# fujiBLEboard.net
KiCad netlist of a schematic drawn in EAGLE
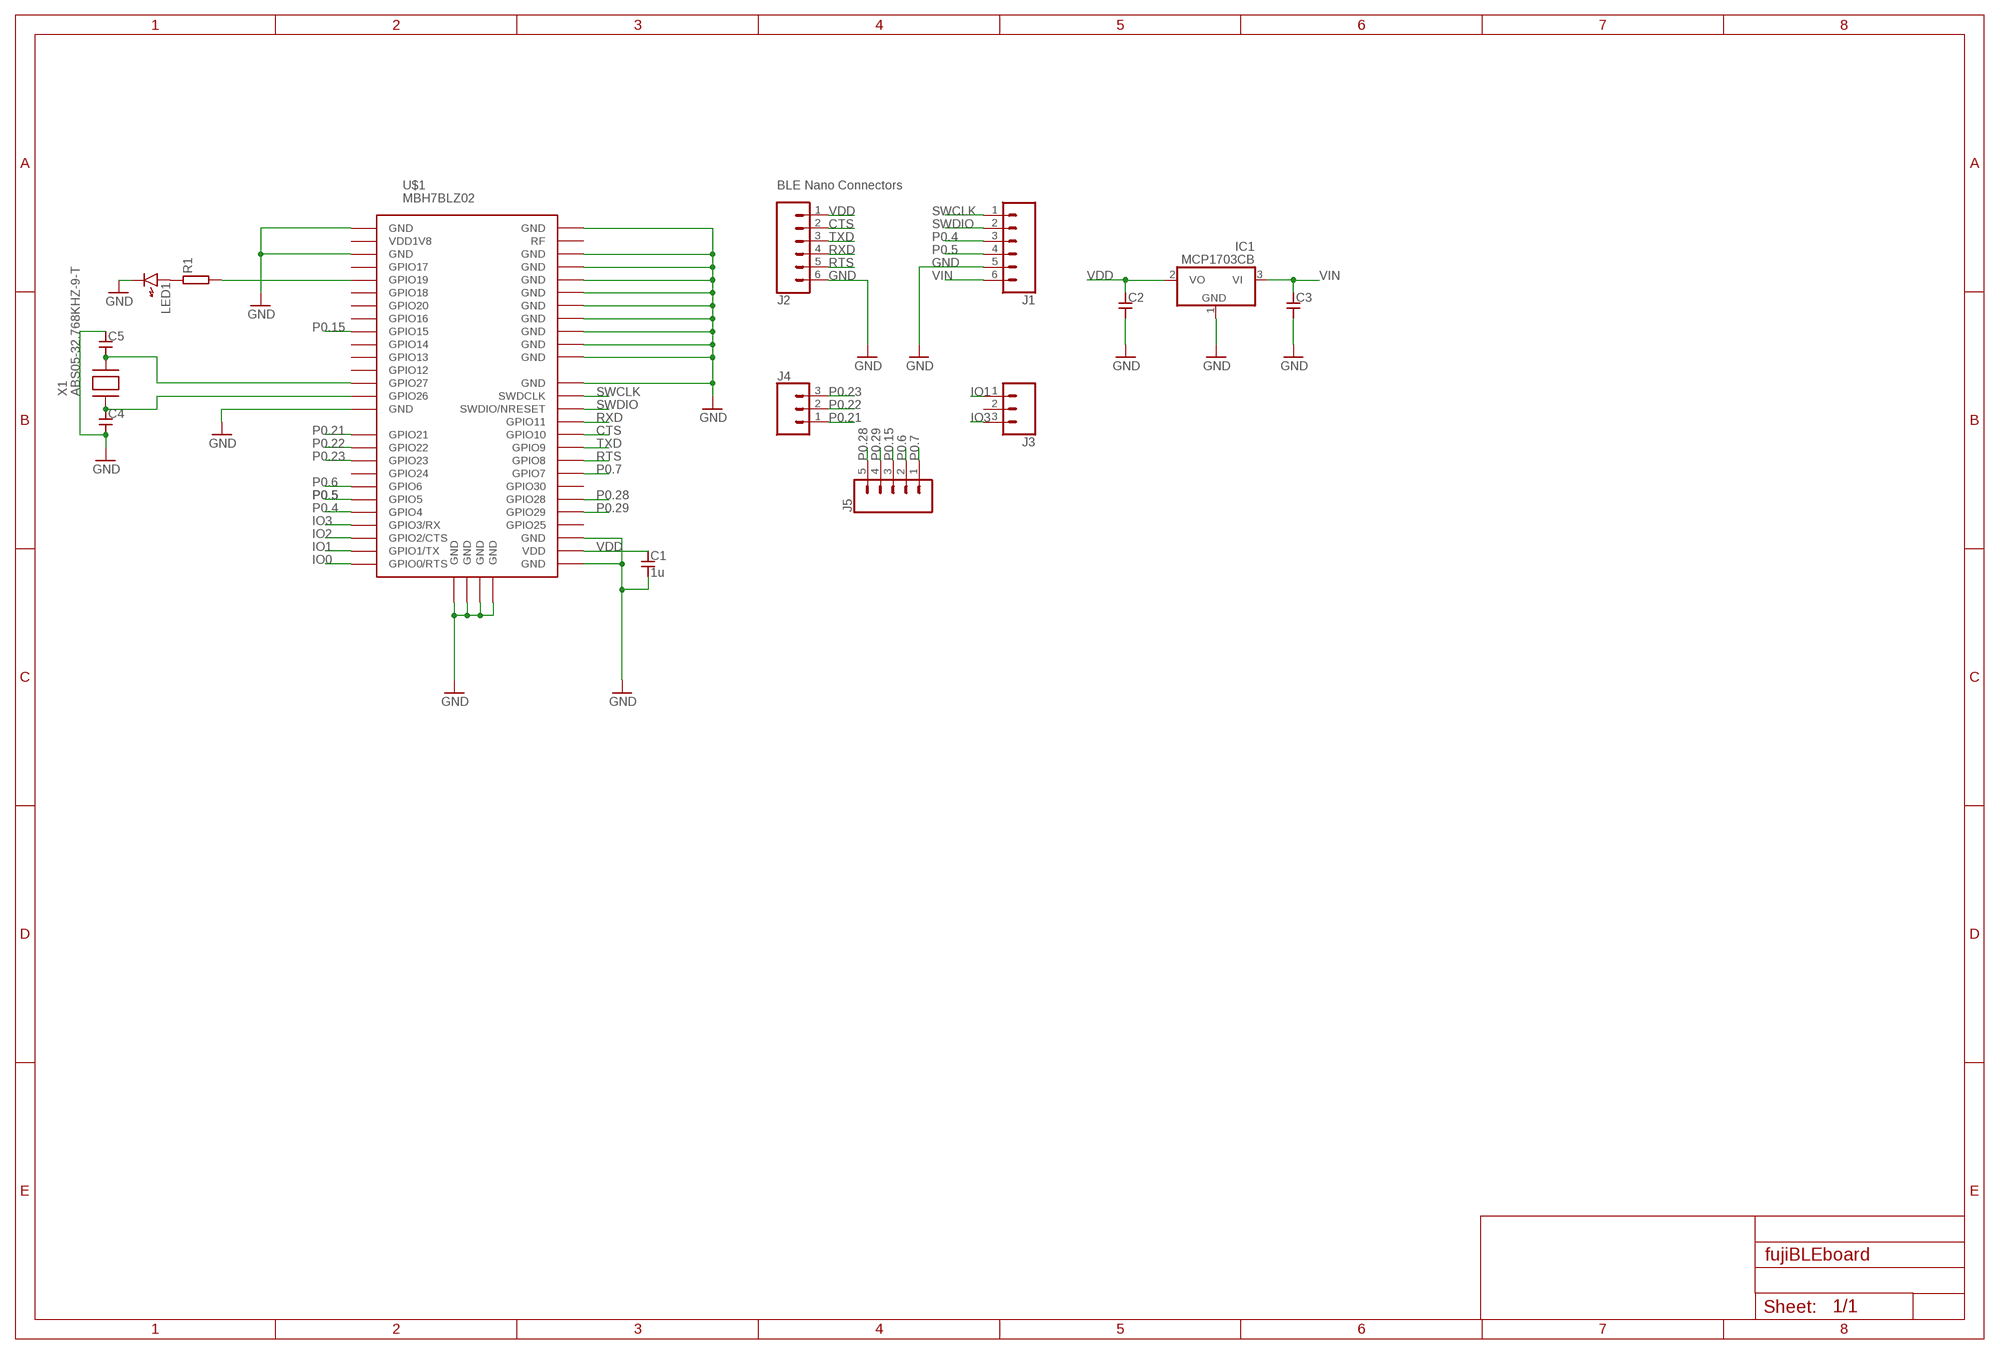
[diagram p0: schematic, sheet 1]

(export (version "E")
  (design (tool "Eeschema 10.0.6"))
  (components
    (comp (ref "C1")
      (value "1u")
      (footprint "eagle-import:SMD1608_REDUCED")
      (libsource (lib "eagle-import") (part "CAPACITOR1608_REDUCED"))
    )
    (comp (ref "C2")
      (value "CAPACITOR1608_REDUCED")
      (footprint "eagle-import:SMD1608_REDUCED")
      (libsource (lib "eagle-import") (part "CAPACITOR1608_REDUCED"))
    )
    (comp (ref "C3")
      (value "CAPACITOR1608_REDUCED")
      (footprint "eagle-import:SMD1608_REDUCED")
      (libsource (lib "eagle-import") (part "CAPACITOR1608_REDUCED"))
    )
    (comp (ref "C4")
      (value "CAPACITOR1005")
      (footprint "eagle-import:SMD1005")
      (libsource (lib "eagle-import") (part "CAPACITOR1005"))
    )
    (comp (ref "C5")
      (value "CAPACITOR1005")
      (footprint "eagle-import:SMD1005")
      (libsource (lib "eagle-import") (part "CAPACITOR1005"))
    )
    (comp (ref "IC1")
      (value "MCP1703CB")
      (footprint "eagle-import:SOT23")
      (libsource (lib "eagle-import") (part "MCP1703CB"))
    )
    (comp (ref "J1")
      (value "CONN_06NO_SILK_FEMALE_PTH")
      (footprint "eagle-import:1X06_NO_SILK")
      (libsource (lib "eagle-import") (part "CONN_06NO_SILK_FEMALE_PTH"))
    )
    (comp (ref "J2")
      (value "CONN_06NO_SILK_FEMALE_PTH")
      (footprint "eagle-import:1X06_NO_SILK")
      (libsource (lib "eagle-import") (part "CONN_06NO_SILK_FEMALE_PTH"))
    )
    (comp (ref "J3")
      (value "CONN_031X03_NO_SILK")
      (footprint "eagle-import:1X03_NO_SILK")
      (libsource (lib "eagle-import") (part "CONN_031X03_NO_SILK"))
    )
    (comp (ref "J4")
      (value "CONN_031X03_NO_SILK")
      (footprint "eagle-import:1X03_NO_SILK")
      (libsource (lib "eagle-import") (part "CONN_031X03_NO_SILK"))
    )
    (comp (ref "J5")
      (value "CONN_05NO_SILK")
      (footprint "eagle-import:1X05_NO_SILK")
      (libsource (lib "eagle-import") (part "CONN_05NO_SILK"))
    )
    (comp (ref "LED1")
      (value "LED1608_REDUCED")
      (footprint "eagle-import:LED1608_REDUCED")
      (libsource (lib "eagle-import") (part "LED1608_REDUCED"))
    )
    (comp (ref "R1")
      (value "RESISTOR1005")
      (footprint "eagle-import:SMD1005")
      (libsource (lib "eagle-import") (part "RESISTOR1005"))
    )
    (comp (ref "U$1")
      (value "MBH7BLZ02")
      (footprint "eagle-import:MBH7BLZ02")
      (libsource (lib "eagle-import") (part "MBH7BLZ02"))
    )
    (comp (ref "X1")
      (value "ABS05-32.768KHZ-9-T")
      (footprint "eagle-import:SMD1610")
      (libsource (lib "eagle-import") (part "ABS05-32.768KHZ-9-T"))
    )
  )
  (nets
    (net (code "1") (name "/CTS") (class "Default")
      (node (ref "J2") (pin "2") (pinfunction "2_2") (pintype "passive"))
      (node (ref "U$1") (pin "P$37") (pinfunction "GPIO10_P$37") (pintype "bidirectional"))
    )
    (net (code "2") (name "/IO0") (class "Default")
      (node (ref "U$1") (pin "P$26") (pinfunction "GPIO0/RTS_P$26") (pintype "bidirectional"))
    )
    (net (code "3") (name "/IO1") (class "Default")
      (node (ref "J3") (pin "1") (pinfunction "1_1") (pintype "passive"))
      (node (ref "U$1") (pin "P$25") (pinfunction "GPIO1/TX_P$25") (pintype "bidirectional"))
    )
    (net (code "4") (name "/IO2") (class "Default")
      (node (ref "U$1") (pin "P$24") (pinfunction "GPIO2/CTS_P$24") (pintype "bidirectional"))
    )
    (net (code "5") (name "/IO3") (class "Default")
      (node (ref "J3") (pin "3") (pinfunction "3_3") (pintype "passive"))
      (node (ref "U$1") (pin "P$23") (pinfunction "GPIO3/RX_P$23") (pintype "bidirectional"))
    )
    (net (code "6") (name "/P0.4") (class "Default")
      (node (ref "J1") (pin "3") (pinfunction "3_3") (pintype "passive"))
      (node (ref "U$1") (pin "P$22") (pinfunction "GPIO4_P$22") (pintype "bidirectional"))
    )
    (net (code "7") (name "/P0.5") (class "Default")
      (node (ref "J1") (pin "4") (pinfunction "4_4") (pintype "passive"))
      (node (ref "U$1") (pin "P$21") (pinfunction "GPIO5_P$21") (pintype "bidirectional"))
    )
    (net (code "8") (name "/P0.6") (class "Default")
      (node (ref "J5") (pin "2") (pinfunction "2_2") (pintype "passive"))
      (node (ref "U$1") (pin "P$20") (pinfunction "GPIO6_P$20") (pintype "bidirectional"))
    )
    (net (code "9") (name "/P0.7") (class "Default")
      (node (ref "J5") (pin "1") (pinfunction "1_1") (pintype "passive"))
      (node (ref "U$1") (pin "P$34") (pinfunction "GPIO7_P$34") (pintype "bidirectional"))
    )
    (net (code "10") (name "/P0.15") (class "Default")
      (node (ref "J5") (pin "3") (pinfunction "3_3") (pintype "passive"))
      (node (ref "U$1") (pin "P$9") (pinfunction "GPIO15_P$9") (pintype "bidirectional"))
    )
    (net (code "11") (name "/P0.21") (class "Default")
      (node (ref "J4") (pin "1") (pinfunction "1_1") (pintype "passive"))
      (node (ref "U$1") (pin "P$16") (pinfunction "GPIO21_P$16") (pintype "bidirectional"))
    )
    (net (code "12") (name "/P0.22") (class "Default")
      (node (ref "J4") (pin "2") (pinfunction "2_2") (pintype "passive"))
      (node (ref "U$1") (pin "P$17") (pinfunction "GPIO22_P$17") (pintype "bidirectional"))
    )
    (net (code "13") (name "/P0.23") (class "Default")
      (node (ref "J4") (pin "3") (pinfunction "3_3") (pintype "passive"))
      (node (ref "U$1") (pin "P$18") (pinfunction "GPIO23_P$18") (pintype "bidirectional"))
    )
    (net (code "14") (name "/P0.28") (class "Default")
      (node (ref "J5") (pin "5") (pinfunction "5_5") (pintype "passive"))
      (node (ref "U$1") (pin "P$32") (pinfunction "GPIO28_P$32") (pintype "bidirectional"))
    )
    (net (code "15") (name "/P0.29") (class "Default")
      (node (ref "J5") (pin "4") (pinfunction "4_4") (pintype "passive"))
      (node (ref "U$1") (pin "P$31") (pinfunction "GPIO29_P$31") (pintype "bidirectional"))
    )
    (net (code "16") (name "/RTS") (class "Default")
      (node (ref "J2") (pin "5") (pinfunction "5_5") (pintype "passive"))
      (node (ref "U$1") (pin "P$35") (pinfunction "GPIO8_P$35") (pintype "bidirectional"))
    )
    (net (code "17") (name "/RXD") (class "Default")
      (node (ref "J2") (pin "4") (pinfunction "4_4") (pintype "passive"))
      (node (ref "U$1") (pin "P$38") (pinfunction "GPIO11_P$38") (pintype "bidirectional"))
    )
    (net (code "18") (name "/SWCLK") (class "Default")
      (node (ref "J1") (pin "1") (pinfunction "1_1") (pintype "passive"))
      (node (ref "U$1") (pin "P$40") (pinfunction "SWDCLK_P$40") (pintype "bidirectional"))
    )
    (net (code "19") (name "/SWDIO") (class "Default")
      (node (ref "J1") (pin "2") (pinfunction "2_2") (pintype "passive"))
      (node (ref "U$1") (pin "P$39") (pinfunction "SWDIO/NRESET_P$39") (pintype "bidirectional"))
    )
    (net (code "20") (name "/TXD") (class "Default")
      (node (ref "J2") (pin "3") (pinfunction "3_3") (pintype "passive"))
      (node (ref "U$1") (pin "P$36") (pinfunction "GPIO9_P$36") (pintype "bidirectional"))
    )
    (net (code "21") (name "/VDD") (class "Default")
      (node (ref "C1") (pin "1") (pinfunction "1_1") (pintype "passive"))
      (node (ref "C2") (pin "1") (pinfunction "1_1") (pintype "passive"))
      (node (ref "IC1") (pin "2") (pinfunction "VO_2") (pintype "passive"))
      (node (ref "J2") (pin "1") (pinfunction "1_1") (pintype "passive"))
      (node (ref "U$1") (pin "P$28") (pinfunction "VDD_P$28") (pintype "bidirectional"))
    )
    (net (code "22") (name "/VIN") (class "Default")
      (node (ref "C3") (pin "1") (pinfunction "1_1") (pintype "passive"))
      (node (ref "IC1") (pin "3") (pinfunction "VI_3") (pintype "input"))
      (node (ref "J1") (pin "6") (pinfunction "6_6") (pintype "passive"))
    )
    (net (code "23") (name "GND") (class "Default")
      (node (ref "C1") (pin "2") (pinfunction "2_2") (pintype "passive"))
      (node (ref "C2") (pin "2") (pinfunction "2_2") (pintype "passive"))
      (node (ref "C3") (pin "2") (pinfunction "2_2") (pintype "passive"))
      (node (ref "C4") (pin "2") (pinfunction "2_2") (pintype "passive"))
      (node (ref "C5") (pin "1") (pinfunction "1_1") (pintype "passive"))
      (node (ref "IC1") (pin "1") (pinfunction "GND_1") (pintype "passive"))
      (node (ref "J1") (pin "5") (pinfunction "5_5") (pintype "passive"))
      (node (ref "J2") (pin "6") (pinfunction "6_6") (pintype "passive"))
      (node (ref "LED1") (pin "K") (pinfunction "K_K") (pintype "passive"))
      (node (ref "U$1") (pin "P$1") (pinfunction "GND_P$1") (pintype "bidirectional"))
      (node (ref "U$1") (pin "P$15") (pinfunction "GND_P$15") (pintype "bidirectional"))
      (node (ref "U$1") (pin "P$27") (pinfunction "GND_P$27") (pintype "bidirectional"))
      (node (ref "U$1") (pin "P$29") (pinfunction "GND_P$29") (pintype "bidirectional"))
      (node (ref "U$1") (pin "P$3") (pinfunction "GND_P$3") (pintype "bidirectional"))
      (node (ref "U$1") (pin "P$41") (pinfunction "GND_P$41") (pintype "bidirectional"))
      (node (ref "U$1") (pin "P$42") (pinfunction "GND_P$42") (pintype "bidirectional"))
      (node (ref "U$1") (pin "P$43") (pinfunction "GND_P$43") (pintype "bidirectional"))
      (node (ref "U$1") (pin "P$44") (pinfunction "GND_P$44") (pintype "bidirectional"))
      (node (ref "U$1") (pin "P$45") (pinfunction "GND_P$45") (pintype "bidirectional"))
      (node (ref "U$1") (pin "P$46") (pinfunction "GND_P$46") (pintype "bidirectional"))
      (node (ref "U$1") (pin "P$47") (pinfunction "GND_P$47") (pintype "bidirectional"))
      (node (ref "U$1") (pin "P$48") (pinfunction "GND_P$48") (pintype "bidirectional"))
      (node (ref "U$1") (pin "P$49") (pinfunction "GND_P$49") (pintype "bidirectional"))
      (node (ref "U$1") (pin "P$50") (pinfunction "GND_P$50") (pintype "bidirectional"))
      (node (ref "U$1") (pin "P$52") (pinfunction "GND_P$52") (pintype "bidirectional"))
      (node (ref "U$1") (pin "P$53") (pinfunction "GND_P$53") (pintype "bidirectional"))
      (node (ref "U$1") (pin "P$54") (pinfunction "GND_P$54") (pintype "bidirectional"))
      (node (ref "U$1") (pin "P$55") (pinfunction "GND_P$55") (pintype "bidirectional"))
      (node (ref "U$1") (pin "P$56") (pinfunction "GND_P$56") (pintype "bidirectional"))
    )
    (net (code "24") (name "Net-(LED1-PadA)") (class "Default")
      (node (ref "LED1") (pin "A") (pinfunction "A_A") (pintype "passive"))
      (node (ref "R1") (pin "1") (pinfunction "1_1") (pintype "passive"))
    )
    (net (code "25") (name "Net-(U$1-GPIO19)") (class "Default")
      (node (ref "R1") (pin "2") (pinfunction "2_2") (pintype "passive"))
      (node (ref "U$1") (pin "P$5") (pinfunction "GPIO19_P$5") (pintype "bidirectional"))
    )
    (net (code "26") (name "Net-(U$1-GPIO26)") (class "Default")
      (node (ref "C4") (pin "1") (pinfunction "1_1") (pintype "passive"))
      (node (ref "U$1") (pin "P$14") (pinfunction "GPIO26_P$14") (pintype "bidirectional"))
      (node (ref "X1") (pin "1") (pinfunction "1_1") (pintype "bidirectional"))
    )
    (net (code "27") (name "Net-(U$1-GPIO27)") (class "Default")
      (node (ref "C5") (pin "2") (pinfunction "2_2") (pintype "passive"))
      (node (ref "U$1") (pin "P$13") (pinfunction "GPIO27_P$13") (pintype "bidirectional"))
      (node (ref "X1") (pin "2") (pinfunction "2_2") (pintype "bidirectional"))
    )
    (net (code "28") (name "unconnected-(J3-Pad2)") (class "Default")
      (node (ref "J3") (pin "2") (pinfunction "2_2") (pintype "passive"))
    )
    (net (code "29") (name "unconnected-(U$1-GPIO12-PadP$12)") (class "Default")
      (node (ref "U$1") (pin "P$12") (pinfunction "GPIO12_P$12") (pintype "bidirectional"))
    )
    (net (code "30") (name "unconnected-(U$1-GPIO13-PadP$11)") (class "Default")
      (node (ref "U$1") (pin "P$11") (pinfunction "GPIO13_P$11") (pintype "bidirectional"))
    )
    (net (code "31") (name "unconnected-(U$1-GPIO14-PadP$10)") (class "Default")
      (node (ref "U$1") (pin "P$10") (pinfunction "GPIO14_P$10") (pintype "bidirectional"))
    )
    (net (code "32") (name "unconnected-(U$1-GPIO16-PadP$8)") (class "Default")
      (node (ref "U$1") (pin "P$8") (pinfunction "GPIO16_P$8") (pintype "bidirectional"))
    )
    (net (code "33") (name "unconnected-(U$1-GPIO17-PadP$4)") (class "Default")
      (node (ref "U$1") (pin "P$4") (pinfunction "GPIO17_P$4") (pintype "bidirectional"))
    )
    (net (code "34") (name "unconnected-(U$1-GPIO18-PadP$6)") (class "Default")
      (node (ref "U$1") (pin "P$6") (pinfunction "GPIO18_P$6") (pintype "bidirectional"))
    )
    (net (code "35") (name "unconnected-(U$1-GPIO20-PadP$7)") (class "Default")
      (node (ref "U$1") (pin "P$7") (pinfunction "GPIO20_P$7") (pintype "bidirectional"))
    )
    (net (code "36") (name "unconnected-(U$1-GPIO24-PadP$19)") (class "Default")
      (node (ref "U$1") (pin "P$19") (pinfunction "GPIO24_P$19") (pintype "bidirectional"))
    )
    (net (code "37") (name "unconnected-(U$1-GPIO25-PadP$30)") (class "Default")
      (node (ref "U$1") (pin "P$30") (pinfunction "GPIO25_P$30") (pintype "bidirectional"))
    )
    (net (code "38") (name "unconnected-(U$1-GPIO30-PadP$33)") (class "Default")
      (node (ref "U$1") (pin "P$33") (pinfunction "GPIO30_P$33") (pintype "bidirectional"))
    )
    (net (code "39") (name "unconnected-(U$1-RF-PadP$51)") (class "Default")
      (node (ref "U$1") (pin "P$51") (pinfunction "RF_P$51") (pintype "bidirectional"))
    )
    (net (code "40") (name "unconnected-(U$1-VDD1V8-PadP$2)") (class "Default")
      (node (ref "U$1") (pin "P$2") (pinfunction "VDD1V8_P$2") (pintype "bidirectional"))
    )
  )
)
